# vaayu.net
KiCad netlist of a schematic drawn in EAGLE
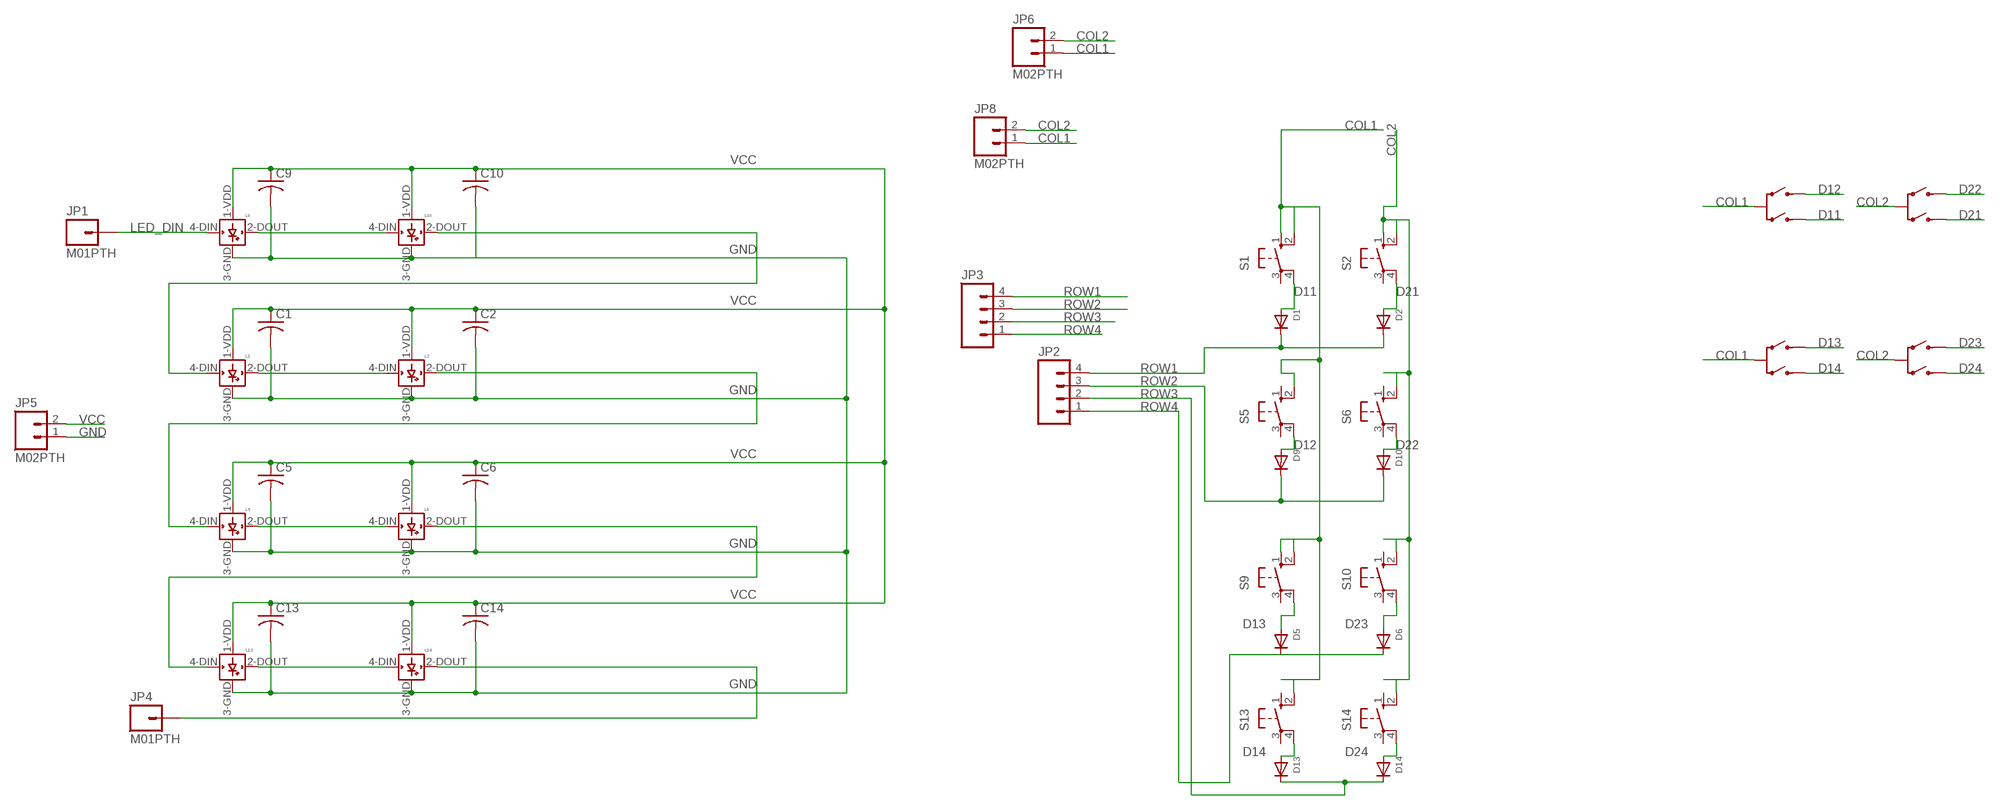
[diagram p0: schematic, sheet 1]

(export (version "E")
  (design (tool "Eeschema 10.0.6"))
  (components
    (comp (ref "C1")
      (value "C-USC1206")
      (footprint "eagle-import:C1206")
      (libsource (lib "eagle-import") (part "C-USC1206"))
    )
    (comp (ref "C2")
      (value "C-USC1206")
      (footprint "eagle-import:C1206")
      (libsource (lib "eagle-import") (part "C-USC1206"))
    )
    (comp (ref "C5")
      (value "C-USC1206")
      (footprint "eagle-import:C1206")
      (libsource (lib "eagle-import") (part "C-USC1206"))
    )
    (comp (ref "C6")
      (value "C-USC1206")
      (footprint "eagle-import:C1206")
      (libsource (lib "eagle-import") (part "C-USC1206"))
    )
    (comp (ref "C9")
      (value "C-USC1206")
      (footprint "eagle-import:C1206")
      (libsource (lib "eagle-import") (part "C-USC1206"))
    )
    (comp (ref "C10")
      (value "C-USC1206")
      (footprint "eagle-import:C1206")
      (libsource (lib "eagle-import") (part "C-USC1206"))
    )
    (comp (ref "C13")
      (value "C-USC1206")
      (footprint "eagle-import:C1206")
      (libsource (lib "eagle-import") (part "C-USC1206"))
    )
    (comp (ref "C14")
      (value "C-USC1206")
      (footprint "eagle-import:C1206")
      (libsource (lib "eagle-import") (part "C-USC1206"))
    )
    (comp (ref "D1")
      (value "DIODESOD-123")
      (footprint "eagle-import:SOD-123")
      (libsource (lib "eagle-import") (part "DIODESOD-123"))
    )
    (comp (ref "D2")
      (value "DIODESOD-123")
      (footprint "eagle-import:SOD-123")
      (libsource (lib "eagle-import") (part "DIODESOD-123"))
    )
    (comp (ref "D5")
      (value "DIODESOD-123")
      (footprint "eagle-import:SOD-123")
      (libsource (lib "eagle-import") (part "DIODESOD-123"))
    )
    (comp (ref "D6")
      (value "DIODESOD-123")
      (footprint "eagle-import:SOD-123")
      (libsource (lib "eagle-import") (part "DIODESOD-123"))
    )
    (comp (ref "D9")
      (value "DIODESOD-123")
      (footprint "eagle-import:SOD-123")
      (libsource (lib "eagle-import") (part "DIODESOD-123"))
    )
    (comp (ref "D10")
      (value "DIODESOD-123")
      (footprint "eagle-import:SOD-123")
      (libsource (lib "eagle-import") (part "DIODESOD-123"))
    )
    (comp (ref "D13")
      (value "DIODESOD-123")
      (footprint "eagle-import:SOD-123")
      (libsource (lib "eagle-import") (part "DIODESOD-123"))
    )
    (comp (ref "D14")
      (value "DIODESOD-123")
      (footprint "eagle-import:SOD-123")
      (libsource (lib "eagle-import") (part "DIODESOD-123"))
    )
    (comp (ref "JP1")
      (value "M01PTH")
      (footprint "eagle-import:1X01")
      (libsource (lib "eagle-import") (part "M01PTH"))
    )
    (comp (ref "JP2")
      (value "M04PTH")
      (footprint "eagle-import:1X04")
      (libsource (lib "eagle-import") (part "M04PTH"))
    )
    (comp (ref "JP3")
      (value "M04PTH")
      (footprint "eagle-import:1X04")
      (libsource (lib "eagle-import") (part "M04PTH"))
    )
    (comp (ref "JP4")
      (value "M01PTH")
      (footprint "eagle-import:1X01")
      (libsource (lib "eagle-import") (part "M01PTH"))
    )
    (comp (ref "JP5")
      (value "M02PTH")
      (footprint "eagle-import:1X02")
      (libsource (lib "eagle-import") (part "M02PTH"))
    )
    (comp (ref "JP6")
      (value "M02PTH")
      (footprint "eagle-import:1X02")
      (libsource (lib "eagle-import") (part "M02PTH"))
    )
    (comp (ref "JP8")
      (value "M02PTH")
      (footprint "eagle-import:1X02")
      (libsource (lib "eagle-import") (part "M02PTH"))
    )
    (comp (ref "L1")
      (value "WS2812B")
      (footprint "eagle-import:WS2812B")
      (libsource (lib "eagle-import") (part "WS2812B"))
    )
    (comp (ref "L2")
      (value "WS2812B")
      (footprint "eagle-import:WS2812B")
      (libsource (lib "eagle-import") (part "WS2812B"))
    )
    (comp (ref "L5")
      (value "WS2812B")
      (footprint "eagle-import:WS2812B")
      (libsource (lib "eagle-import") (part "WS2812B"))
    )
    (comp (ref "L6")
      (value "WS2812B")
      (footprint "eagle-import:WS2812B")
      (libsource (lib "eagle-import") (part "WS2812B"))
    )
    (comp (ref "L9")
      (value "WS2812B")
      (footprint "eagle-import:WS2812B")
      (libsource (lib "eagle-import") (part "WS2812B"))
    )
    (comp (ref "L10")
      (value "WS2812B")
      (footprint "eagle-import:WS2812B")
      (libsource (lib "eagle-import") (part "WS2812B"))
    )
    (comp (ref "L13")
      (value "WS2812B")
      (footprint "eagle-import:WS2812B")
      (libsource (lib "eagle-import") (part "WS2812B"))
    )
    (comp (ref "L14")
      (value "WS2812B")
      (footprint "eagle-import:WS2812B")
      (libsource (lib "eagle-import") (part "WS2812B"))
    )
    (comp (ref "S1")
      (value "10-XX")
      (footprint "eagle-import:B3F-10XX")
      (fields (field (name "MPN") "B3F-1000"))
      (libsource (lib "eagle-import") (part "10-XX"))
    )
    (comp (ref "S2")
      (value "10-XX")
      (footprint "eagle-import:B3F-10XX")
      (fields (field (name "MPN") "B3F-1000"))
      (libsource (lib "eagle-import") (part "10-XX"))
    )
    (comp (ref "S5")
      (value "10-XX")
      (footprint "eagle-import:B3F-10XX")
      (fields (field (name "MPN") "B3F-1000"))
      (libsource (lib "eagle-import") (part "10-XX"))
    )
    (comp (ref "S6")
      (value "10-XX")
      (footprint "eagle-import:B3F-10XX")
      (fields (field (name "MPN") "B3F-1000"))
      (libsource (lib "eagle-import") (part "10-XX"))
    )
    (comp (ref "S9")
      (value "10-XX")
      (footprint "eagle-import:B3F-10XX")
      (fields (field (name "MPN") "B3F-1000"))
      (libsource (lib "eagle-import") (part "10-XX"))
    )
    (comp (ref "S10")
      (value "10-XX")
      (footprint "eagle-import:B3F-10XX")
      (fields (field (name "MPN") "B3F-1000"))
      (libsource (lib "eagle-import") (part "10-XX"))
    )
    (comp (ref "S13")
      (value "10-XX")
      (footprint "eagle-import:B3F-10XX")
      (fields (field (name "MPN") "B3F-1000"))
      (libsource (lib "eagle-import") (part "10-XX"))
    )
    (comp (ref "S14")
      (value "10-XX")
      (footprint "eagle-import:B3F-10XX")
      (fields (field (name "MPN") "B3F-1000"))
      (libsource (lib "eagle-import") (part "10-XX"))
    )
    (comp (ref "U$1")
      (value "ALPHA-ROT-ENCODER")
      (footprint "eagle-import:TW-700198")
      (libsource (lib "eagle-import") (part "ALPHA-ROT-ENCODER"))
    )
    (comp (ref "U$4")
      (value "ALPHA-ROT-ENCODER")
      (footprint "eagle-import:TW-700198")
      (libsource (lib "eagle-import") (part "ALPHA-ROT-ENCODER"))
    )
    (comp (ref "U$5")
      (value "ALPHA-ROT-ENCODER")
      (footprint "eagle-import:TW-700198")
      (libsource (lib "eagle-import") (part "ALPHA-ROT-ENCODER"))
    )
    (comp (ref "U$8")
      (value "ALPHA-ROT-ENCODER")
      (footprint "eagle-import:TW-700198")
      (libsource (lib "eagle-import") (part "ALPHA-ROT-ENCODER"))
    )
  )
  (nets
    (net (code "1") (name "/COL1") (class "Default")
      (node (ref "JP6") (pin "1") (pinfunction "1_1") (pintype "passive"))
      (node (ref "JP8") (pin "1") (pinfunction "1_1") (pintype "passive"))
      (node (ref "S1") (pin "1") (pinfunction "S_1") (pintype "passive"))
      (node (ref "S1") (pin "2") (pinfunction "S1_2") (pintype "passive"))
      (node (ref "S13") (pin "2") (pinfunction "S1_2") (pintype "passive"))
      (node (ref "S5") (pin "2") (pinfunction "S1_2") (pintype "passive"))
      (node (ref "S9") (pin "1") (pinfunction "S_1") (pintype "passive"))
      (node (ref "S9") (pin "2") (pinfunction "S1_2") (pintype "passive"))
      (node (ref "U$4") (pin "P2") (pinfunction "COM_P2") (pintype "passive"))
      (node (ref "U$8") (pin "P2") (pinfunction "COM_P2") (pintype "passive"))
    )
    (net (code "2") (name "/COL2") (class "Default")
      (node (ref "JP6") (pin "2") (pinfunction "2_2") (pintype "passive"))
      (node (ref "JP8") (pin "2") (pinfunction "2_2") (pintype "passive"))
      (node (ref "S10") (pin "2") (pinfunction "S1_2") (pintype "passive"))
      (node (ref "S14") (pin "2") (pinfunction "S1_2") (pintype "passive"))
      (node (ref "S2") (pin "1") (pinfunction "S_1") (pintype "passive"))
      (node (ref "S2") (pin "2") (pinfunction "S1_2") (pintype "passive"))
      (node (ref "S6") (pin "2") (pinfunction "S1_2") (pintype "passive"))
      (node (ref "U$1") (pin "P2") (pinfunction "COM_P2") (pintype "passive"))
      (node (ref "U$5") (pin "P2") (pinfunction "COM_P2") (pintype "passive"))
    )
    (net (code "3") (name "/D11") (class "Default")
      (node (ref "D1") (pin "A") (pinfunction "A_A") (pintype "passive"))
      (node (ref "S1") (pin "4") (pinfunction "P1_4") (pintype "passive"))
      (node (ref "U$4") (pin "P1") (pinfunction "B_P1") (pintype "passive"))
    )
    (net (code "4") (name "/D12") (class "Default")
      (node (ref "D9") (pin "A") (pinfunction "A_A") (pintype "passive"))
      (node (ref "S5") (pin "4") (pinfunction "P1_4") (pintype "passive"))
      (node (ref "U$4") (pin "P3") (pinfunction "A_P3") (pintype "passive"))
    )
    (net (code "5") (name "/D13") (class "Default")
      (node (ref "D5") (pin "A") (pinfunction "A_A") (pintype "passive"))
      (node (ref "S9") (pin "4") (pinfunction "P1_4") (pintype "passive"))
      (node (ref "U$8") (pin "P3") (pinfunction "A_P3") (pintype "passive"))
    )
    (net (code "6") (name "/D14") (class "Default")
      (node (ref "D13") (pin "A") (pinfunction "A_A") (pintype "passive"))
      (node (ref "S13") (pin "4") (pinfunction "P1_4") (pintype "passive"))
      (node (ref "U$8") (pin "P1") (pinfunction "B_P1") (pintype "passive"))
    )
    (net (code "7") (name "/D21") (class "Default")
      (node (ref "D2") (pin "A") (pinfunction "A_A") (pintype "passive"))
      (node (ref "S2") (pin "4") (pinfunction "P1_4") (pintype "passive"))
      (node (ref "U$1") (pin "P1") (pinfunction "B_P1") (pintype "passive"))
    )
    (net (code "8") (name "/D22") (class "Default")
      (node (ref "D10") (pin "A") (pinfunction "A_A") (pintype "passive"))
      (node (ref "S6") (pin "4") (pinfunction "P1_4") (pintype "passive"))
      (node (ref "U$1") (pin "P3") (pinfunction "A_P3") (pintype "passive"))
    )
    (net (code "9") (name "/D23") (class "Default")
      (node (ref "D6") (pin "A") (pinfunction "A_A") (pintype "passive"))
      (node (ref "S10") (pin "4") (pinfunction "P1_4") (pintype "passive"))
      (node (ref "U$5") (pin "P3") (pinfunction "A_P3") (pintype "passive"))
    )
    (net (code "10") (name "/D24") (class "Default")
      (node (ref "D14") (pin "A") (pinfunction "A_A") (pintype "passive"))
      (node (ref "S14") (pin "4") (pinfunction "P1_4") (pintype "passive"))
      (node (ref "U$5") (pin "P1") (pinfunction "B_P1") (pintype "passive"))
    )
    (net (code "11") (name "/GND") (class "Default")
      (node (ref "C1") (pin "2") (pinfunction "2_2") (pintype "passive"))
      (node (ref "C10") (pin "2") (pinfunction "2_2") (pintype "passive"))
      (node (ref "C13") (pin "2") (pinfunction "2_2") (pintype "passive"))
      (node (ref "C14") (pin "2") (pinfunction "2_2") (pintype "passive"))
      (node (ref "C2") (pin "2") (pinfunction "2_2") (pintype "passive"))
      (node (ref "C5") (pin "2") (pinfunction "2_2") (pintype "passive"))
      (node (ref "C6") (pin "2") (pinfunction "2_2") (pintype "passive"))
      (node (ref "C9") (pin "2") (pinfunction "2_2") (pintype "passive"))
      (node (ref "JP5") (pin "1") (pinfunction "1_1") (pintype "passive"))
      (node (ref "L1") (pin "3-GND") (pinfunction "GND_3-GND") (pintype "bidirectional"))
      (node (ref "L10") (pin "3-GND") (pinfunction "GND_3-GND") (pintype "bidirectional"))
      (node (ref "L13") (pin "3-GND") (pinfunction "GND_3-GND") (pintype "bidirectional"))
      (node (ref "L14") (pin "3-GND") (pinfunction "GND_3-GND") (pintype "bidirectional"))
      (node (ref "L2") (pin "3-GND") (pinfunction "GND_3-GND") (pintype "bidirectional"))
      (node (ref "L5") (pin "3-GND") (pinfunction "GND_3-GND") (pintype "bidirectional"))
      (node (ref "L6") (pin "3-GND") (pinfunction "GND_3-GND") (pintype "bidirectional"))
      (node (ref "L9") (pin "3-GND") (pinfunction "GND_3-GND") (pintype "bidirectional"))
    )
    (net (code "12") (name "/LED_DIN") (class "Default")
      (node (ref "JP1") (pin "1") (pinfunction "1_1") (pintype "passive"))
      (node (ref "L9") (pin "4-DIN") (pinfunction "DIN_4-DIN") (pintype "input"))
    )
    (net (code "13") (name "/ROW1") (class "Default")
      (node (ref "D1") (pin "C") (pinfunction "C_C") (pintype "passive"))
      (node (ref "D2") (pin "C") (pinfunction "C_C") (pintype "passive"))
      (node (ref "JP2") (pin "4") (pinfunction "4_4") (pintype "passive"))
      (node (ref "JP3") (pin "4") (pinfunction "4_4") (pintype "passive"))
    )
    (net (code "14") (name "/ROW2") (class "Default")
      (node (ref "D10") (pin "C") (pinfunction "C_C") (pintype "passive"))
      (node (ref "D9") (pin "C") (pinfunction "C_C") (pintype "passive"))
      (node (ref "JP2") (pin "3") (pinfunction "3_3") (pintype "passive"))
      (node (ref "JP3") (pin "3") (pinfunction "3_3") (pintype "passive"))
    )
    (net (code "15") (name "/ROW3") (class "Default")
      (node (ref "D13") (pin "C") (pinfunction "C_C") (pintype "passive"))
      (node (ref "D14") (pin "C") (pinfunction "C_C") (pintype "passive"))
      (node (ref "JP2") (pin "2") (pinfunction "2_2") (pintype "passive"))
      (node (ref "JP3") (pin "2") (pinfunction "2_2") (pintype "passive"))
    )
    (net (code "16") (name "/ROW4") (class "Default")
      (node (ref "D5") (pin "C") (pinfunction "C_C") (pintype "passive"))
      (node (ref "D6") (pin "C") (pinfunction "C_C") (pintype "passive"))
      (node (ref "JP2") (pin "1") (pinfunction "1_1") (pintype "passive"))
      (node (ref "JP3") (pin "1") (pinfunction "1_1") (pintype "passive"))
    )
    (net (code "17") (name "/VCC") (class "Default")
      (node (ref "C1") (pin "1") (pinfunction "1_1") (pintype "passive"))
      (node (ref "C10") (pin "1") (pinfunction "1_1") (pintype "passive"))
      (node (ref "C13") (pin "1") (pinfunction "1_1") (pintype "passive"))
      (node (ref "C14") (pin "1") (pinfunction "1_1") (pintype "passive"))
      (node (ref "C2") (pin "1") (pinfunction "1_1") (pintype "passive"))
      (node (ref "C5") (pin "1") (pinfunction "1_1") (pintype "passive"))
      (node (ref "C6") (pin "1") (pinfunction "1_1") (pintype "passive"))
      (node (ref "C9") (pin "1") (pinfunction "1_1") (pintype "passive"))
      (node (ref "JP5") (pin "2") (pinfunction "2_2") (pintype "passive"))
      (node (ref "L1") (pin "1-VDD") (pinfunction "VDD_1-VDD") (pintype "bidirectional"))
      (node (ref "L10") (pin "1-VDD") (pinfunction "VDD_1-VDD") (pintype "bidirectional"))
      (node (ref "L13") (pin "1-VDD") (pinfunction "VDD_1-VDD") (pintype "bidirectional"))
      (node (ref "L14") (pin "1-VDD") (pinfunction "VDD_1-VDD") (pintype "bidirectional"))
      (node (ref "L2") (pin "1-VDD") (pinfunction "VDD_1-VDD") (pintype "bidirectional"))
      (node (ref "L5") (pin "1-VDD") (pinfunction "VDD_1-VDD") (pintype "bidirectional"))
      (node (ref "L6") (pin "1-VDD") (pinfunction "VDD_1-VDD") (pintype "bidirectional"))
      (node (ref "L9") (pin "1-VDD") (pinfunction "VDD_1-VDD") (pintype "bidirectional"))
    )
    (net (code "18") (name "Net-(L1-DIN)") (class "Default")
      (node (ref "L1") (pin "4-DIN") (pinfunction "DIN_4-DIN") (pintype "input"))
      (node (ref "L10") (pin "2-DOUT") (pinfunction "DOUT_2-DOUT") (pintype "output"))
    )
    (net (code "19") (name "Net-(L1-DOUT)") (class "Default")
      (node (ref "L1") (pin "2-DOUT") (pinfunction "DOUT_2-DOUT") (pintype "output"))
      (node (ref "L2") (pin "4-DIN") (pinfunction "DIN_4-DIN") (pintype "input"))
    )
    (net (code "20") (name "Net-(L2-DOUT)") (class "Default")
      (node (ref "L2") (pin "2-DOUT") (pinfunction "DOUT_2-DOUT") (pintype "output"))
      (node (ref "L5") (pin "4-DIN") (pinfunction "DIN_4-DIN") (pintype "input"))
    )
    (net (code "21") (name "Net-(L5-DOUT)") (class "Default")
      (node (ref "L5") (pin "2-DOUT") (pinfunction "DOUT_2-DOUT") (pintype "output"))
      (node (ref "L6") (pin "4-DIN") (pinfunction "DIN_4-DIN") (pintype "input"))
    )
    (net (code "22") (name "Net-(L10-DIN)") (class "Default")
      (node (ref "L10") (pin "4-DIN") (pinfunction "DIN_4-DIN") (pintype "input"))
      (node (ref "L9") (pin "2-DOUT") (pinfunction "DOUT_2-DOUT") (pintype "output"))
    )
    (net (code "23") (name "Net-(L13-DIN)") (class "Default")
      (node (ref "L13") (pin "4-DIN") (pinfunction "DIN_4-DIN") (pintype "input"))
      (node (ref "L6") (pin "2-DOUT") (pinfunction "DOUT_2-DOUT") (pintype "output"))
    )
    (net (code "24") (name "Net-(L13-DOUT)") (class "Default")
      (node (ref "L13") (pin "2-DOUT") (pinfunction "DOUT_2-DOUT") (pintype "output"))
      (node (ref "L14") (pin "4-DIN") (pinfunction "DIN_4-DIN") (pintype "input"))
    )
    (net (code "25") (name "Net-(L14-DOUT)") (class "Default")
      (node (ref "JP4") (pin "1") (pinfunction "1_1") (pintype "passive"))
      (node (ref "L14") (pin "2-DOUT") (pinfunction "DOUT_2-DOUT") (pintype "output"))
    )
    (net (code "26") (name "unconnected-(S1-P-Pad3)") (class "Default")
      (node (ref "S1") (pin "3") (pinfunction "P_3") (pintype "passive"))
    )
    (net (code "27") (name "unconnected-(S2-P-Pad3)") (class "Default")
      (node (ref "S2") (pin "3") (pinfunction "P_3") (pintype "passive"))
    )
    (net (code "28") (name "unconnected-(S5-P-Pad3)") (class "Default")
      (node (ref "S5") (pin "3") (pinfunction "P_3") (pintype "passive"))
    )
    (net (code "29") (name "unconnected-(S5-S-Pad1)") (class "Default")
      (node (ref "S5") (pin "1") (pinfunction "S_1") (pintype "passive"))
    )
    (net (code "30") (name "unconnected-(S6-P-Pad3)") (class "Default")
      (node (ref "S6") (pin "3") (pinfunction "P_3") (pintype "passive"))
    )
    (net (code "31") (name "unconnected-(S6-S-Pad1)") (class "Default")
      (node (ref "S6") (pin "1") (pinfunction "S_1") (pintype "passive"))
    )
    (net (code "32") (name "unconnected-(S9-P-Pad3)") (class "Default")
      (node (ref "S9") (pin "3") (pinfunction "P_3") (pintype "passive"))
    )
    (net (code "33") (name "unconnected-(S10-P-Pad3)") (class "Default")
      (node (ref "S10") (pin "3") (pinfunction "P_3") (pintype "passive"))
    )
    (net (code "34") (name "unconnected-(S10-S-Pad1)") (class "Default")
      (node (ref "S10") (pin "1") (pinfunction "S_1") (pintype "passive"))
    )
    (net (code "35") (name "unconnected-(S13-P-Pad3)") (class "Default")
      (node (ref "S13") (pin "3") (pinfunction "P_3") (pintype "passive"))
    )
    (net (code "36") (name "unconnected-(S13-S-Pad1)") (class "Default")
      (node (ref "S13") (pin "1") (pinfunction "S_1") (pintype "passive"))
    )
    (net (code "37") (name "unconnected-(S14-P-Pad3)") (class "Default")
      (node (ref "S14") (pin "3") (pinfunction "P_3") (pintype "passive"))
    )
    (net (code "38") (name "unconnected-(S14-S-Pad1)") (class "Default")
      (node (ref "S14") (pin "1") (pinfunction "S_1") (pintype "passive"))
    )
  )
)
